# dual_sensor_module.net
KiCad netlist of a schematic drawn in EAGLE
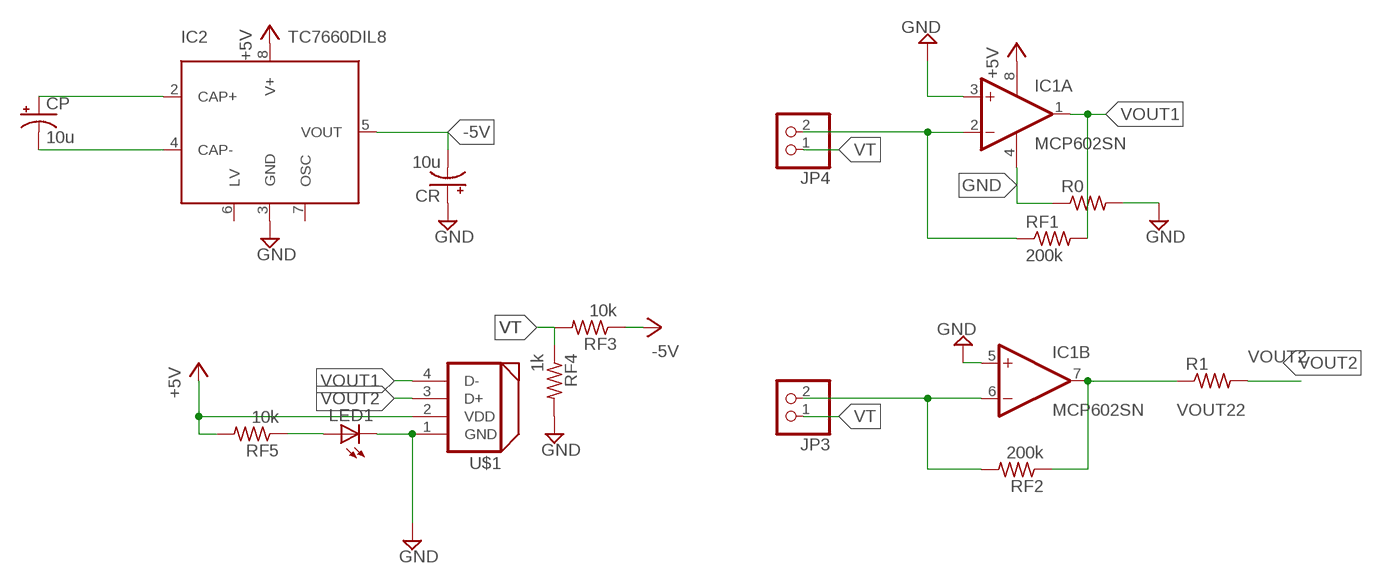
[diagram p0: schematic, sheet 1]

(export (version "E")
  (design (tool "Eeschema 10.0.6"))
  (components
    (comp (ref "CP")
      (value "10u")
      (footprint "eagle-import:E2,5-5")
      (libsource (lib "eagle-import") (part "CPOL-USE2.5-5"))
    )
    (comp (ref "CR")
      (value "10u")
      (footprint "eagle-import:E2,5-5")
      (libsource (lib "eagle-import") (part "CPOL-USE2.5-5"))
    )
    (comp (ref "IC1")
      (value "MCP602SN")
      (footprint "eagle-import:SO08")
      (libsource (lib "eagle-import") (part "MCP602SN"))
    )
    (comp (ref "IC2")
      (value "TC7660DIL8")
      (footprint "eagle-import:DIL8")
      (libsource (lib "eagle-import") (part "TC7660DIL8"))
    )
    (comp (ref "JP3")
      (value "PINHD-1X2")
      (footprint "eagle-import:1X02")
      (libsource (lib "eagle-import") (part "PINHD-1X2"))
    )
    (comp (ref "JP4")
      (value "PINHD-1X2")
      (footprint "eagle-import:1X02")
      (libsource (lib "eagle-import") (part "PINHD-1X2"))
    )
    (comp (ref "LED1")
      (value "LED3MM")
      (footprint "eagle-import:LED3MM")
      (libsource (lib "eagle-import") (part "LED3MM"))
    )
    (comp (ref "R0")
      (value "R-US_R1206")
      (footprint "eagle-import:R1206")
      (libsource (lib "eagle-import") (part "R-US_R1206"))
    )
    (comp (ref "R1")
      (value "R-US_R1206")
      (footprint "eagle-import:R1206")
      (libsource (lib "eagle-import") (part "R-US_R1206"))
    )
    (comp (ref "RF1")
      (value "200k")
      (footprint "eagle-import:R0805")
      (libsource (lib "eagle-import") (part "resistor_348_R-US_R0805"))
    )
    (comp (ref "RF2")
      (value "200k")
      (footprint "eagle-import:R0805")
      (libsource (lib "eagle-import") (part "resistor_348_R-US_R0805"))
    )
    (comp (ref "RF3")
      (value "10k")
      (footprint "eagle-import:R0805")
      (libsource (lib "eagle-import") (part "resistor_348_R-US_R0805"))
    )
    (comp (ref "RF4")
      (value "1k")
      (footprint "eagle-import:R0805")
      (libsource (lib "eagle-import") (part "resistor_348_R-US_R0805"))
    )
    (comp (ref "RF5")
      (value "10k")
      (footprint "eagle-import:R0805")
      (libsource (lib "eagle-import") (part "resistor_348_R-US_R0805"))
    )
    (comp (ref "U$1")
      (value "DYNAMIXEL_RS485")
      (footprint "eagle-import:DYNAMIXEL_SPOX_04")
      (libsource (lib "eagle-import") (part "DYNAMIXEL_RS485"))
    )
  )
  (nets
    (net (code "1") (name "+5V") (class "Default")
      (node (ref "IC1") (pin "8") (pinfunction "V+_8") (pintype "power_in"))
      (node (ref "IC2") (pin "8") (pinfunction "V+_8") (pintype "bidirectional"))
      (node (ref "RF5") (pin "2") (pinfunction "2_2") (pintype "passive"))
      (node (ref "U$1") (pin "2") (pinfunction "VDD_2") (pintype "power_in"))
    )
    (net (code "2") (name "-5V") (class "Default")
      (node (ref "CR") (pin "-") (pinfunction "-_-") (pintype "passive"))
      (node (ref "IC2") (pin "5") (pinfunction "VOUT_5") (pintype "bidirectional"))
      (node (ref "RF3") (pin "1") (pinfunction "1_1") (pintype "passive"))
    )
    (net (code "3") (name "/VOUT22") (class "Default")
      (node (ref "IC1") (pin "7") (pinfunction "OUT_7") (pintype "output"))
      (node (ref "R1") (pin "1") (pinfunction "1_1") (pintype "passive"))
      (node (ref "RF2") (pin "1") (pinfunction "1_1") (pintype "passive"))
    )
    (net (code "4") (name "GND") (class "Default")
      (node (ref "CR") (pin "+") (pinfunction "+_+") (pintype "passive"))
      (node (ref "IC1") (pin "3") (pinfunction "+IN_3") (pintype "input"))
      (node (ref "IC1") (pin "4") (pinfunction "V-_4") (pintype "power_in"))
      (node (ref "IC1") (pin "5") (pinfunction "+IN_5") (pintype "input"))
      (node (ref "IC2") (pin "3") (pinfunction "GND_3") (pintype "bidirectional"))
      (node (ref "LED1") (pin "K") (pinfunction "C_K") (pintype "passive"))
      (node (ref "R0") (pin "1") (pinfunction "1_1") (pintype "passive"))
      (node (ref "R0") (pin "2") (pinfunction "2_2") (pintype "passive"))
      (node (ref "RF4") (pin "2") (pinfunction "2_2") (pintype "passive"))
      (node (ref "U$1") (pin "1") (pinfunction "GND_1") (pintype "power_in"))
    )
    (net (code "5") (name "Net-(IC1A--IN)") (class "Default")
      (node (ref "IC1") (pin "2") (pinfunction "-IN_2") (pintype "input"))
      (node (ref "JP4") (pin "2") (pinfunction "2_2") (pintype "passive"))
      (node (ref "RF1") (pin "1") (pinfunction "1_1") (pintype "passive"))
    )
    (net (code "6") (name "Net-(IC1B--IN)") (class "Default")
      (node (ref "IC1") (pin "6") (pinfunction "-IN_6") (pintype "input"))
      (node (ref "JP3") (pin "2") (pinfunction "2_2") (pintype "passive"))
      (node (ref "RF2") (pin "2") (pinfunction "2_2") (pintype "passive"))
    )
    (net (code "7") (name "Net-(IC2-CAP+)") (class "Default")
      (node (ref "CP") (pin "+") (pinfunction "+_+") (pintype "passive"))
      (node (ref "IC2") (pin "2") (pinfunction "CAP+_2") (pintype "bidirectional"))
    )
    (net (code "8") (name "Net-(IC2-CAP-)") (class "Default")
      (node (ref "CP") (pin "-") (pinfunction "-_-") (pintype "passive"))
      (node (ref "IC2") (pin "4") (pinfunction "CAP-_4") (pintype "bidirectional"))
    )
    (net (code "9") (name "Net-(LED1-PadA)") (class "Default")
      (node (ref "LED1") (pin "A") (pinfunction "A_A") (pintype "passive"))
      (node (ref "RF5") (pin "1") (pinfunction "1_1") (pintype "passive"))
    )
    (net (code "10") (name "VOUT1") (class "Default")
      (node (ref "IC1") (pin "1") (pinfunction "OUT_1") (pintype "output"))
      (node (ref "RF1") (pin "2") (pinfunction "2_2") (pintype "passive"))
      (node (ref "U$1") (pin "4") (pinfunction "D-_4") (pintype "bidirectional"))
    )
    (net (code "11") (name "VOUT2") (class "Default")
      (node (ref "R1") (pin "2") (pinfunction "2_2") (pintype "passive"))
      (node (ref "U$1") (pin "3") (pinfunction "D+_3") (pintype "bidirectional"))
    )
    (net (code "12") (name "VT") (class "Default")
      (node (ref "JP3") (pin "1") (pinfunction "1_1") (pintype "passive"))
      (node (ref "JP4") (pin "1") (pinfunction "1_1") (pintype "passive"))
      (node (ref "RF3") (pin "2") (pinfunction "2_2") (pintype "passive"))
      (node (ref "RF4") (pin "1") (pinfunction "1_1") (pintype "passive"))
    )
    (net (code "13") (name "unconnected-(IC2-LV-Pad6)") (class "Default")
      (node (ref "IC2") (pin "6") (pinfunction "LV_6") (pintype "bidirectional"))
    )
    (net (code "14") (name "unconnected-(IC2-OSC-Pad7)") (class "Default")
      (node (ref "IC2") (pin "7") (pinfunction "OSC_7") (pintype "bidirectional"))
    )
  )
)
